# hello-soldering-0_3.net
KiCad netlist of a schematic drawn in EAGLE
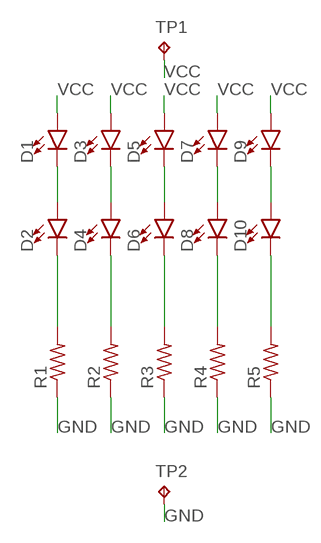
[diagram p0: schematic, sheet 1]

(export (version "E")
  (design (tool "Eeschema 10.0.6"))
  (components
    (comp (ref "D1")
      (value "LED1206")
      (footprint "eagle-import:LED-1206")
      (libsource (lib "eagle-import") (part "LED1206"))
    )
    (comp (ref "D2")
      (value "LED1206")
      (footprint "eagle-import:LED-1206")
      (libsource (lib "eagle-import") (part "LED1206"))
    )
    (comp (ref "D3")
      (value "LED1206")
      (footprint "eagle-import:LED-1206")
      (libsource (lib "eagle-import") (part "LED1206"))
    )
    (comp (ref "D4")
      (value "LED1206")
      (footprint "eagle-import:LED-1206")
      (libsource (lib "eagle-import") (part "LED1206"))
    )
    (comp (ref "D5")
      (value "LED1206")
      (footprint "eagle-import:LED-1206")
      (libsource (lib "eagle-import") (part "LED1206"))
    )
    (comp (ref "D6")
      (value "LED1206")
      (footprint "eagle-import:LED-1206")
      (libsource (lib "eagle-import") (part "LED1206"))
    )
    (comp (ref "D7")
      (value "LED1206")
      (footprint "eagle-import:LED-1206")
      (libsource (lib "eagle-import") (part "LED1206"))
    )
    (comp (ref "D8")
      (value "LED1206")
      (footprint "eagle-import:LED-1206")
      (libsource (lib "eagle-import") (part "LED1206"))
    )
    (comp (ref "D9")
      (value "LED1206")
      (footprint "eagle-import:LED-1206")
      (libsource (lib "eagle-import") (part "LED1206"))
    )
    (comp (ref "D10")
      (value "LED1206")
      (footprint "eagle-import:LED-1206")
      (libsource (lib "eagle-import") (part "LED1206"))
    )
    (comp (ref "R1")
      (value "RES-US1206")
      (footprint "eagle-import:R1206")
      (libsource (lib "eagle-import") (part "RES-US1206"))
    )
    (comp (ref "R2")
      (value "RES-US1206")
      (footprint "eagle-import:R1206")
      (libsource (lib "eagle-import") (part "RES-US1206"))
    )
    (comp (ref "R3")
      (value "RES-US1206")
      (footprint "eagle-import:R1206")
      (libsource (lib "eagle-import") (part "RES-US1206"))
    )
    (comp (ref "R4")
      (value "RES-US1206")
      (footprint "eagle-import:R1206")
      (libsource (lib "eagle-import") (part "RES-US1206"))
    )
    (comp (ref "R5")
      (value "RES-US1206")
      (footprint "eagle-import:R1206")
      (libsource (lib "eagle-import") (part "RES-US1206"))
    )
    (comp (ref "TP1")
      (value "TPTP20R")
      (footprint "eagle-import:TP20R")
      (libsource (lib "eagle-import") (part "TPTP20R"))
    )
    (comp (ref "TP2")
      (value "TPTP20R")
      (footprint "eagle-import:TP20R")
      (libsource (lib "eagle-import") (part "TPTP20R"))
    )
  )
  (nets
    (net (code "1") (name "/GND") (class "Default")
      (node (ref "R1") (pin "1") (pinfunction "1_1") (pintype "passive"))
      (node (ref "R2") (pin "1") (pinfunction "1_1") (pintype "passive"))
      (node (ref "R3") (pin "1") (pinfunction "1_1") (pintype "passive"))
      (node (ref "R4") (pin "1") (pinfunction "1_1") (pintype "passive"))
      (node (ref "R5") (pin "1") (pinfunction "1_1") (pintype "passive"))
      (node (ref "TP2") (pin "TP") (pinfunction "TP_TP") (pintype "input"))
    )
    (net (code "2") (name "/VCC") (class "Default")
      (node (ref "D1") (pin "A") (pinfunction "A_A") (pintype "passive"))
      (node (ref "D3") (pin "A") (pinfunction "A_A") (pintype "passive"))
      (node (ref "D5") (pin "A") (pinfunction "A_A") (pintype "passive"))
      (node (ref "D7") (pin "A") (pinfunction "A_A") (pintype "passive"))
      (node (ref "D9") (pin "A") (pinfunction "A_A") (pintype "passive"))
      (node (ref "TP1") (pin "TP") (pinfunction "TP_TP") (pintype "input"))
    )
    (net (code "3") (name "Net-(D1-PadC)") (class "Default")
      (node (ref "D1") (pin "C") (pinfunction "C_C") (pintype "passive"))
      (node (ref "D2") (pin "A") (pinfunction "A_A") (pintype "passive"))
    )
    (net (code "4") (name "Net-(D2-PadC)") (class "Default")
      (node (ref "D2") (pin "C") (pinfunction "C_C") (pintype "passive"))
      (node (ref "R1") (pin "2") (pinfunction "2_2") (pintype "passive"))
    )
    (net (code "5") (name "Net-(D3-PadC)") (class "Default")
      (node (ref "D3") (pin "C") (pinfunction "C_C") (pintype "passive"))
      (node (ref "D4") (pin "A") (pinfunction "A_A") (pintype "passive"))
    )
    (net (code "6") (name "Net-(D4-PadC)") (class "Default")
      (node (ref "D4") (pin "C") (pinfunction "C_C") (pintype "passive"))
      (node (ref "R2") (pin "2") (pinfunction "2_2") (pintype "passive"))
    )
    (net (code "7") (name "Net-(D5-PadC)") (class "Default")
      (node (ref "D5") (pin "C") (pinfunction "C_C") (pintype "passive"))
      (node (ref "D6") (pin "A") (pinfunction "A_A") (pintype "passive"))
    )
    (net (code "8") (name "Net-(D6-PadC)") (class "Default")
      (node (ref "D6") (pin "C") (pinfunction "C_C") (pintype "passive"))
      (node (ref "R3") (pin "2") (pinfunction "2_2") (pintype "passive"))
    )
    (net (code "9") (name "Net-(D7-PadC)") (class "Default")
      (node (ref "D7") (pin "C") (pinfunction "C_C") (pintype "passive"))
      (node (ref "D8") (pin "A") (pinfunction "A_A") (pintype "passive"))
    )
    (net (code "10") (name "Net-(D8-PadC)") (class "Default")
      (node (ref "D8") (pin "C") (pinfunction "C_C") (pintype "passive"))
      (node (ref "R4") (pin "2") (pinfunction "2_2") (pintype "passive"))
    )
    (net (code "11") (name "Net-(D10-PadA)") (class "Default")
      (node (ref "D10") (pin "A") (pinfunction "A_A") (pintype "passive"))
      (node (ref "D9") (pin "C") (pinfunction "C_C") (pintype "passive"))
    )
    (net (code "12") (name "Net-(D10-PadC)") (class "Default")
      (node (ref "D10") (pin "C") (pinfunction "C_C") (pintype "passive"))
      (node (ref "R5") (pin "2") (pinfunction "2_2") (pintype "passive"))
    )
  )
)
